# Sheet2.net
KiCad netlist of a schematic drawn in Altium Designer
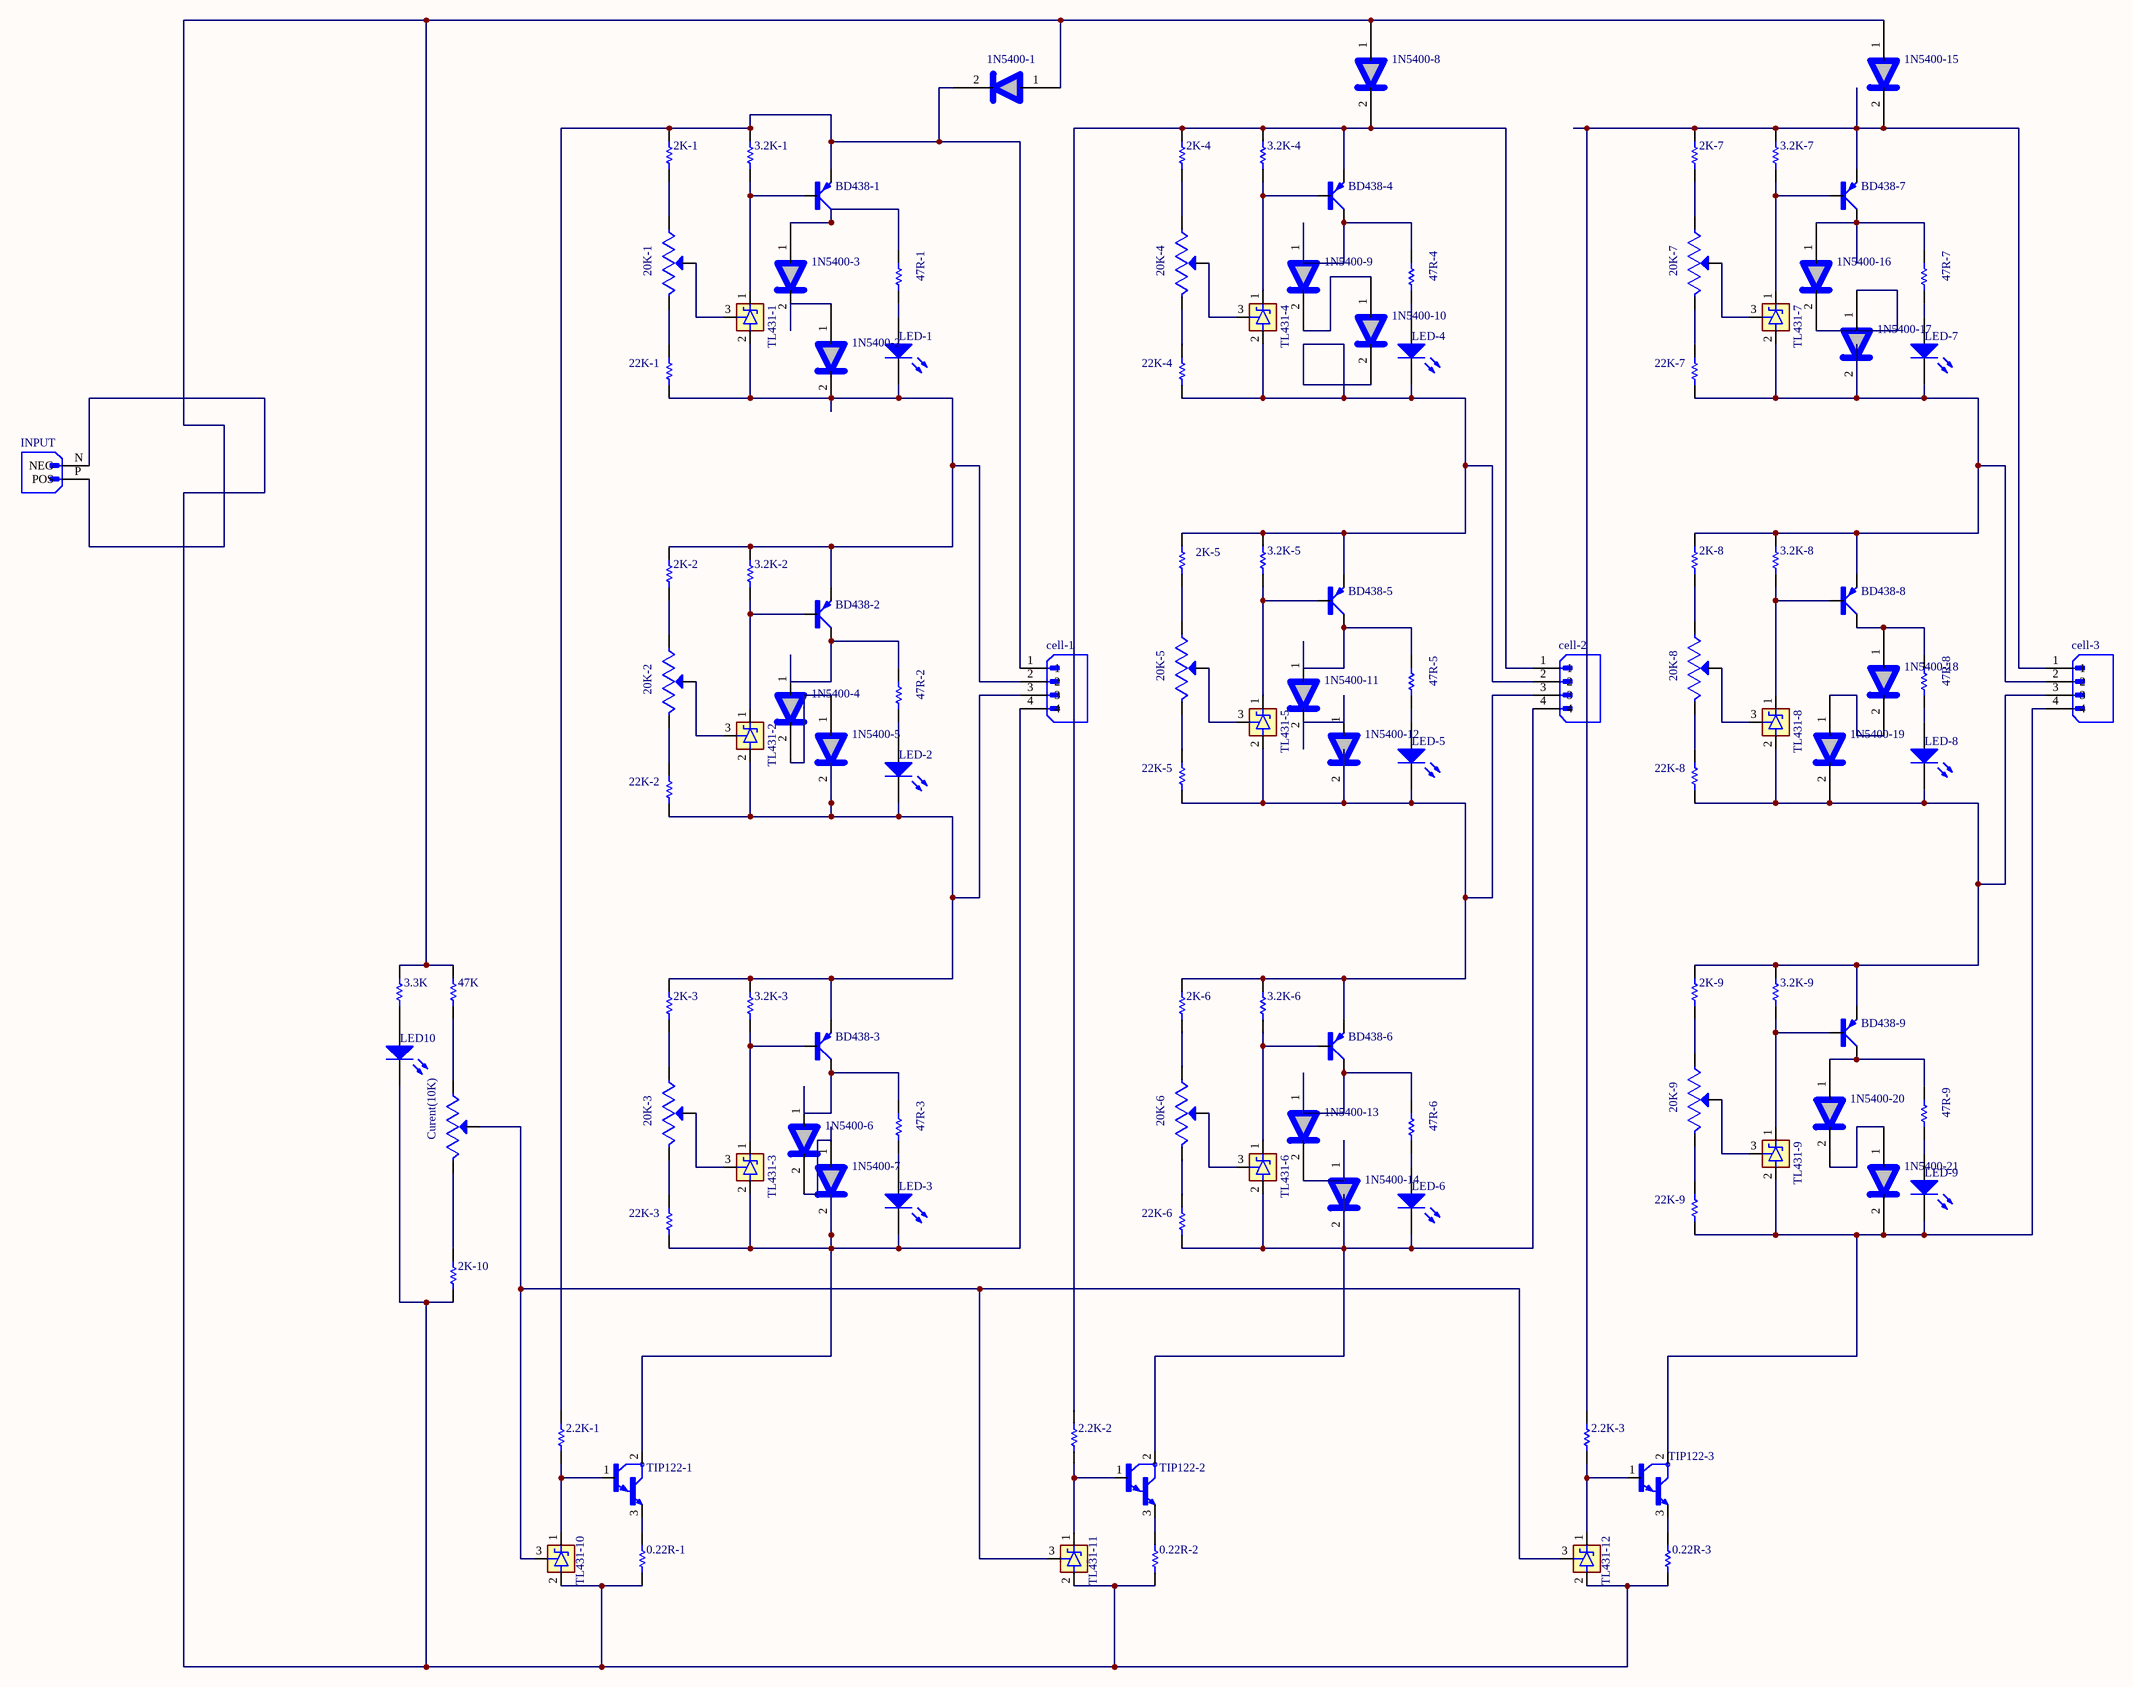
[diagram p0: Sheet2.SchDoc]

(export (version "E")
  (design (tool "Eeschema 10.0.6"))
  (components
    (comp (ref "0.22R-1")
      (value "~")
      (footprint "AXIAL-0.3")
      (description "Resistor")
      (fields (field (name "PUBLISHER") "Altium Limited"))
      (libsource (lib "Miscellaneous Devices") (part "Res1"))
    )
    (comp (ref "0.22R-2")
      (value "~")
      (footprint "AXIAL-0.3")
      (description "Resistor")
      (fields (field (name "PUBLISHER") "Altium Limited"))
      (libsource (lib "Miscellaneous Devices") (part "Res1"))
    )
    (comp (ref "0.22R-3")
      (value "~")
      (footprint "AXIAL-0.3")
      (description "Resistor")
      (fields (field (name "PUBLISHER") "Altium Limited"))
      (libsource (lib "Miscellaneous Devices") (part "Res1"))
    )
    (comp (ref "1N5400-1")
      (value "~")
      (footprint "PCBComponent_1")
      (libsource (lib "Schlib1") (part "1N5400-"))
    )
    (comp (ref "1N5400-2")
      (value "~")
      (footprint "PCBComponent_1")
      (libsource (lib "Schlib1") (part "1N5400-"))
    )
    (comp (ref "1N5400-3")
      (value "~")
      (footprint "PCBComponent_1")
      (libsource (lib "Schlib1") (part "1N5400-"))
    )
    (comp (ref "1N5400-4")
      (value "~")
      (footprint "PCBComponent_1")
      (libsource (lib "Schlib1") (part "1N5400-"))
    )
    (comp (ref "1N5400-5")
      (value "~")
      (footprint "PCBComponent_1")
      (libsource (lib "Schlib1") (part "1N5400-"))
    )
    (comp (ref "1N5400-6")
      (value "~")
      (footprint "PCBComponent_1")
      (libsource (lib "Schlib1") (part "1N5400-"))
    )
    (comp (ref "1N5400-7")
      (value "~")
      (footprint "PCBComponent_1")
      (libsource (lib "Schlib1") (part "1N5400-"))
    )
    (comp (ref "1N5400-8")
      (value "~")
      (footprint "PCBComponent_1")
      (libsource (lib "Schlib1") (part "1N5400-"))
    )
    (comp (ref "1N5400-9")
      (value "~")
      (footprint "PCBComponent_1")
      (libsource (lib "Schlib1") (part "1N5400-"))
    )
    (comp (ref "1N5400-10")
      (value "~")
      (footprint "PCBComponent_1")
      (libsource (lib "Schlib1") (part "1N5400-"))
    )
    (comp (ref "1N5400-11")
      (value "~")
      (footprint "PCBComponent_1")
      (libsource (lib "Schlib1") (part "1N5400-"))
    )
    (comp (ref "1N5400-12")
      (value "~")
      (footprint "PCBComponent_1")
      (libsource (lib "Schlib1") (part "1N5400-"))
    )
    (comp (ref "1N5400-13")
      (value "~")
      (footprint "PCBComponent_1")
      (libsource (lib "Schlib1") (part "1N5400-"))
    )
    (comp (ref "1N5400-14")
      (value "~")
      (footprint "PCBComponent_1")
      (libsource (lib "Schlib1") (part "1N5400-"))
    )
    (comp (ref "1N5400-15")
      (value "~")
      (footprint "PCBComponent_1")
      (libsource (lib "Schlib1") (part "1N5400-"))
    )
    (comp (ref "1N5400-16")
      (value "~")
      (footprint "PCBComponent_1")
      (libsource (lib "Schlib1") (part "1N5400-"))
    )
    (comp (ref "1N5400-17")
      (value "~")
      (footprint "PCBComponent_1")
      (libsource (lib "Schlib1") (part "1N5400-"))
    )
    (comp (ref "1N5400-18")
      (value "~")
      (footprint "PCBComponent_1")
      (libsource (lib "Schlib1") (part "1N5400-"))
    )
    (comp (ref "1N5400-19")
      (value "~")
      (footprint "PCBComponent_1")
      (libsource (lib "Schlib1") (part "1N5400-"))
    )
    (comp (ref "1N5400-20")
      (value "~")
      (footprint "PCBComponent_1")
      (libsource (lib "Schlib1") (part "1N5400-"))
    )
    (comp (ref "1N5400-21")
      (value "~")
      (footprint "PCBComponent_1")
      (libsource (lib "Schlib1") (part "1N5400-"))
    )
    (comp (ref "2.2K-1")
      (value "~")
      (footprint "AXIAL-0.3")
      (description "Resistor")
      (fields (field (name "PUBLISHER") "Altium Limited"))
      (libsource (lib "Miscellaneous Devices") (part "Res1"))
    )
    (comp (ref "2.2K-2")
      (value "~")
      (footprint "AXIAL-0.3")
      (description "Resistor")
      (fields (field (name "PUBLISHER") "Altium Limited"))
      (libsource (lib "Miscellaneous Devices") (part "Res1"))
    )
    (comp (ref "2.2K-3")
      (value "~")
      (footprint "AXIAL-0.3")
      (description "Resistor")
      (fields (field (name "PUBLISHER") "Altium Limited"))
      (libsource (lib "Miscellaneous Devices") (part "Res1"))
    )
    (comp (ref "2K-1")
      (value "~")
      (footprint "AXIAL-0.3")
      (description "Resistor")
      (fields (field (name "PUBLISHER") "Altium Limited"))
      (libsource (lib "Miscellaneous Devices") (part "Res1"))
    )
    (comp (ref "2K-2")
      (value "~")
      (footprint "AXIAL-0.3")
      (description "Resistor")
      (fields (field (name "PUBLISHER") "Altium Limited"))
      (libsource (lib "Miscellaneous Devices") (part "Res1"))
    )
    (comp (ref "2K-3")
      (value "~")
      (footprint "AXIAL-0.3")
      (description "Resistor")
      (fields (field (name "PUBLISHER") "Altium Limited"))
      (libsource (lib "Miscellaneous Devices") (part "Res1"))
    )
    (comp (ref "2K-4")
      (value "~")
      (footprint "AXIAL-0.3")
      (description "Resistor")
      (fields (field (name "PUBLISHER") "Altium Limited"))
      (libsource (lib "Miscellaneous Devices") (part "Res1"))
    )
    (comp (ref "2K-5")
      (value "~")
      (footprint "AXIAL-0.3")
      (description "Resistor")
      (fields (field (name "PUBLISHER") "Altium Limited"))
      (libsource (lib "Miscellaneous Devices") (part "Res1"))
    )
    (comp (ref "2K-6")
      (value "~")
      (footprint "AXIAL-0.3")
      (description "Resistor")
      (fields (field (name "PUBLISHER") "Altium Limited"))
      (libsource (lib "Miscellaneous Devices") (part "Res1"))
    )
    (comp (ref "2K-7")
      (value "~")
      (footprint "AXIAL-0.3")
      (description "Resistor")
      (fields (field (name "PUBLISHER") "Altium Limited"))
      (libsource (lib "Miscellaneous Devices") (part "Res1"))
    )
    (comp (ref "2K-8")
      (value "~")
      (footprint "AXIAL-0.3")
      (description "Resistor")
      (fields (field (name "PUBLISHER") "Altium Limited"))
      (libsource (lib "Miscellaneous Devices") (part "Res1"))
    )
    (comp (ref "2K-9")
      (value "~")
      (footprint "AXIAL-0.3")
      (description "Resistor")
      (fields (field (name "PUBLISHER") "Altium Limited"))
      (libsource (lib "Miscellaneous Devices") (part "Res1"))
    )
    (comp (ref "2K-10")
      (value "~")
      (footprint "AXIAL-0.3")
      (description "Resistor")
      (fields (field (name "PUBLISHER") "Altium Limited"))
      (libsource (lib "Miscellaneous Devices") (part "Res1"))
    )
    (comp (ref "3.2K-1")
      (value "~")
      (footprint "AXIAL-0.3")
      (description "Resistor")
      (fields (field (name "PUBLISHER") "Altium Limited"))
      (libsource (lib "Miscellaneous Devices") (part "Res1"))
    )
    (comp (ref "3.2K-2")
      (value "~")
      (footprint "AXIAL-0.3")
      (description "Resistor")
      (fields (field (name "PUBLISHER") "Altium Limited"))
      (libsource (lib "Miscellaneous Devices") (part "Res1"))
    )
    (comp (ref "3.2K-3")
      (value "~")
      (footprint "AXIAL-0.3")
      (description "Resistor")
      (fields (field (name "PUBLISHER") "Altium Limited"))
      (libsource (lib "Miscellaneous Devices") (part "Res1"))
    )
    (comp (ref "3.2K-4")
      (value "~")
      (footprint "AXIAL-0.3")
      (description "Resistor")
      (fields (field (name "PUBLISHER") "Altium Limited"))
      (libsource (lib "Miscellaneous Devices") (part "Res1"))
    )
    (comp (ref "3.2K-5")
      (value "~")
      (footprint "AXIAL-0.3")
      (description "Resistor")
      (fields (field (name "PUBLISHER") "Altium Limited"))
      (libsource (lib "Miscellaneous Devices") (part "Res1"))
    )
    (comp (ref "3.2K-6")
      (value "~")
      (footprint "AXIAL-0.3")
      (description "Resistor")
      (fields (field (name "PUBLISHER") "Altium Limited"))
      (libsource (lib "Miscellaneous Devices") (part "Res1"))
    )
    (comp (ref "3.2K-7")
      (value "~")
      (footprint "AXIAL-0.3")
      (description "Resistor")
      (fields (field (name "PUBLISHER") "Altium Limited"))
      (libsource (lib "Miscellaneous Devices") (part "Res1"))
    )
    (comp (ref "3.2K-8")
      (value "~")
      (footprint "AXIAL-0.3")
      (description "Resistor")
      (fields (field (name "PUBLISHER") "Altium Limited"))
      (libsource (lib "Miscellaneous Devices") (part "Res1"))
    )
    (comp (ref "3.2K-9")
      (value "~")
      (footprint "AXIAL-0.3")
      (description "Resistor")
      (fields (field (name "PUBLISHER") "Altium Limited"))
      (libsource (lib "Miscellaneous Devices") (part "Res1"))
    )
    (comp (ref "3.3K")
      (value "~")
      (footprint "AXIAL-0.3")
      (description "Resistor")
      (fields (field (name "PUBLISHER") "Altium Limited"))
      (libsource (lib "Miscellaneous Devices") (part "Res1"))
    )
    (comp (ref "20K-1")
      (value "~")
      (footprint "TRIM_3296W-FM1-502")
      (description "Trimmer Resistors - Through Hole")
      (fields (field (name "MP") "3296W-FM1-502") (field (name "MF") "Bourns"))
      (libsource (lib "3296W-FM1-502") (part "3296W-FM1-502"))
    )
    (comp (ref "20K-2")
      (value "~")
      (footprint "TRIM_3296W-FM1-502")
      (description "Trimmer Resistors - Through Hole")
      (fields (field (name "MP") "3296W-FM1-502") (field (name "MF") "Bourns"))
      (libsource (lib "3296W-FM1-502") (part "3296W-FM1-502"))
    )
    (comp (ref "20K-3")
      (value "~")
      (footprint "TRIM_3296W-FM1-502")
      (description "Trimmer Resistors - Through Hole")
      (fields (field (name "MP") "3296W-FM1-502") (field (name "MF") "Bourns"))
      (libsource (lib "3296W-FM1-502") (part "3296W-FM1-502"))
    )
    (comp (ref "20K-4")
      (value "~")
      (footprint "TRIM_3296W-FM1-502")
      (description "Trimmer Resistors - Through Hole")
      (fields (field (name "MP") "3296W-FM1-502") (field (name "MF") "Bourns"))
      (libsource (lib "3296W-FM1-502") (part "3296W-FM1-502"))
    )
    (comp (ref "20K-5")
      (value "~")
      (footprint "TRIM_3296W-FM1-502")
      (description "Trimmer Resistors - Through Hole")
      (fields (field (name "MP") "3296W-FM1-502") (field (name "MF") "Bourns"))
      (libsource (lib "3296W-FM1-502") (part "3296W-FM1-502"))
    )
    (comp (ref "20K-6")
      (value "~")
      (footprint "TRIM_3296W-FM1-502")
      (description "Trimmer Resistors - Through Hole")
      (fields (field (name "MP") "3296W-FM1-502") (field (name "MF") "Bourns"))
      (libsource (lib "3296W-FM1-502") (part "3296W-FM1-502"))
    )
    (comp (ref "20K-7")
      (value "~")
      (footprint "TRIM_3296W-FM1-502")
      (description "Trimmer Resistors - Through Hole")
      (fields (field (name "MP") "3296W-FM1-502") (field (name "MF") "Bourns"))
      (libsource (lib "3296W-FM1-502") (part "3296W-FM1-502"))
    )
    (comp (ref "20K-8")
      (value "~")
      (footprint "TRIM_3296W-FM1-502")
      (description "Trimmer Resistors - Through Hole")
      (fields (field (name "MP") "3296W-FM1-502") (field (name "MF") "Bourns"))
      (libsource (lib "3296W-FM1-502") (part "3296W-FM1-502"))
    )
    (comp (ref "20K-9")
      (value "~")
      (footprint "TRIM_3296W-FM1-502")
      (description "Trimmer Resistors - Through Hole")
      (fields (field (name "MP") "3296W-FM1-502") (field (name "MF") "Bourns"))
      (libsource (lib "3296W-FM1-502") (part "3296W-FM1-502"))
    )
    (comp (ref "22K-1")
      (value "~")
      (footprint "AXIAL-0.3")
      (description "Resistor")
      (fields (field (name "PUBLISHER") "Altium Limited"))
      (libsource (lib "Miscellaneous Devices") (part "Res1"))
    )
    (comp (ref "22K-2")
      (value "~")
      (footprint "AXIAL-0.3")
      (description "Resistor")
      (fields (field (name "PUBLISHER") "Altium Limited"))
      (libsource (lib "Miscellaneous Devices") (part "Res1"))
    )
    (comp (ref "22K-3")
      (value "~")
      (footprint "AXIAL-0.3")
      (description "Resistor")
      (fields (field (name "PUBLISHER") "Altium Limited"))
      (libsource (lib "Miscellaneous Devices") (part "Res1"))
    )
    (comp (ref "22K-4")
      (value "~")
      (footprint "AXIAL-0.3")
      (description "Resistor")
      (fields (field (name "PUBLISHER") "Altium Limited"))
      (libsource (lib "Miscellaneous Devices") (part "Res1"))
    )
    (comp (ref "22K-5")
      (value "~")
      (footprint "AXIAL-0.3")
      (description "Resistor")
      (fields (field (name "PUBLISHER") "Altium Limited"))
      (libsource (lib "Miscellaneous Devices") (part "Res1"))
    )
    (comp (ref "22K-6")
      (value "~")
      (footprint "AXIAL-0.3")
      (description "Resistor")
      (fields (field (name "PUBLISHER") "Altium Limited"))
      (libsource (lib "Miscellaneous Devices") (part "Res1"))
    )
    (comp (ref "22K-7")
      (value "~")
      (footprint "AXIAL-0.3")
      (description "Resistor")
      (fields (field (name "PUBLISHER") "Altium Limited"))
      (libsource (lib "Miscellaneous Devices") (part "Res1"))
    )
    (comp (ref "22K-8")
      (value "~")
      (footprint "AXIAL-0.3")
      (description "Resistor")
      (fields (field (name "PUBLISHER") "Altium Limited"))
      (libsource (lib "Miscellaneous Devices") (part "Res1"))
    )
    (comp (ref "22K-9")
      (value "~")
      (footprint "AXIAL-0.3")
      (description "Resistor")
      (fields (field (name "PUBLISHER") "Altium Limited"))
      (libsource (lib "Miscellaneous Devices") (part "Res1"))
    )
    (comp (ref "47K")
      (value "~")
      (footprint "AXIAL-0.3")
      (description "Resistor")
      (fields (field (name "PUBLISHER") "Altium Limited"))
      (libsource (lib "Miscellaneous Devices") (part "Res1"))
    )
    (comp (ref "47R-1")
      (value "~")
      (footprint "AXIAL-0.3")
      (description "Resistor")
      (fields (field (name "PUBLISHER") "Altium Limited"))
      (libsource (lib "Miscellaneous Devices") (part "Res1"))
    )
    (comp (ref "47R-2")
      (value "~")
      (footprint "AXIAL-0.3")
      (description "Resistor")
      (fields (field (name "PUBLISHER") "Altium Limited"))
      (libsource (lib "Miscellaneous Devices") (part "Res1"))
    )
    (comp (ref "47R-3")
      (value "~")
      (footprint "AXIAL-0.3")
      (description "Resistor")
      (fields (field (name "PUBLISHER") "Altium Limited"))
      (libsource (lib "Miscellaneous Devices") (part "Res1"))
    )
    (comp (ref "47R-4")
      (value "~")
      (footprint "AXIAL-0.3")
      (description "Resistor")
      (fields (field (name "PUBLISHER") "Altium Limited"))
      (libsource (lib "Miscellaneous Devices") (part "Res1"))
    )
    (comp (ref "47R-5")
      (value "~")
      (footprint "AXIAL-0.3")
      (description "Resistor")
      (fields (field (name "PUBLISHER") "Altium Limited"))
      (libsource (lib "Miscellaneous Devices") (part "Res1"))
    )
    (comp (ref "47R-6")
      (value "~")
      (footprint "AXIAL-0.3")
      (description "Resistor")
      (fields (field (name "PUBLISHER") "Altium Limited"))
      (libsource (lib "Miscellaneous Devices") (part "Res1"))
    )
    (comp (ref "47R-7")
      (value "~")
      (footprint "AXIAL-0.3")
      (description "Resistor")
      (fields (field (name "PUBLISHER") "Altium Limited"))
      (libsource (lib "Miscellaneous Devices") (part "Res1"))
    )
    (comp (ref "47R-8")
      (value "~")
      (footprint "AXIAL-0.3")
      (description "Resistor")
      (fields (field (name "PUBLISHER") "Altium Limited"))
      (libsource (lib "Miscellaneous Devices") (part "Res1"))
    )
    (comp (ref "47R-9")
      (value "~")
      (footprint "AXIAL-0.3")
      (description "Resistor")
      (fields (field (name "PUBLISHER") "Altium Limited"))
      (libsource (lib "Miscellaneous Devices") (part "Res1"))
    )
    (comp (ref "BD438-1")
      (value "~")
      (footprint "TO126AV")
      (description "Bipolar (BJT) Transistor PNP 45V 4A 3MHz 36W Through Hole SOT-32-3")
      (fields (field (name "MF") "ON") (field (name "MP") "BD438"))
      (libsource (lib "BD438") (part "BD438"))
    )
    (comp (ref "BD438-2")
      (value "~")
      (footprint "TO126AV")
      (description "Bipolar (BJT) Transistor PNP 45V 4A 3MHz 36W Through Hole SOT-32-3")
      (fields (field (name "MF") "ON") (field (name "MP") "BD438"))
      (libsource (lib "BD438") (part "BD438"))
    )
    (comp (ref "BD438-3")
      (value "~")
      (footprint "TO126AV")
      (description "Bipolar (BJT) Transistor PNP 45V 4A 3MHz 36W Through Hole SOT-32-3")
      (fields (field (name "MF") "ON") (field (name "MP") "BD438"))
      (libsource (lib "BD438") (part "BD438"))
    )
    (comp (ref "BD438-4")
      (value "~")
      (footprint "TO126AV")
      (description "Bipolar (BJT) Transistor PNP 45V 4A 3MHz 36W Through Hole SOT-32-3")
      (fields (field (name "MF") "ON") (field (name "MP") "BD438"))
      (libsource (lib "BD438") (part "BD438"))
    )
    (comp (ref "BD438-5")
      (value "~")
      (footprint "TO126AV")
      (description "Bipolar (BJT) Transistor PNP 45V 4A 3MHz 36W Through Hole SOT-32-3")
      (fields (field (name "MF") "ON") (field (name "MP") "BD438"))
      (libsource (lib "BD438") (part "BD438"))
    )
    (comp (ref "BD438-6")
      (value "~")
      (footprint "TO126AV")
      (description "Bipolar (BJT) Transistor PNP 45V 4A 3MHz 36W Through Hole SOT-32-3")
      (fields (field (name "MF") "ON") (field (name "MP") "BD438"))
      (libsource (lib "BD438") (part "BD438"))
    )
    (comp (ref "BD438-7")
      (value "~")
      (footprint "TO126AV")
      (description "Bipolar (BJT) Transistor PNP 45V 4A 3MHz 36W Through Hole SOT-32-3")
      (fields (field (name "MF") "ON") (field (name "MP") "BD438"))
      (libsource (lib "BD438") (part "BD438"))
    )
    (comp (ref "BD438-8")
      (value "~")
      (footprint "TO126AV")
      (description "Bipolar (BJT) Transistor PNP 45V 4A 3MHz 36W Through Hole SOT-32-3")
      (fields (field (name "MF") "ON") (field (name "MP") "BD438"))
      (libsource (lib "BD438") (part "BD438"))
    )
    (comp (ref "BD438-9")
      (value "~")
      (footprint "TO126AV")
      (description "Bipolar (BJT) Transistor PNP 45V 4A 3MHz 36W Through Hole SOT-32-3")
      (fields (field (name "MF") "ON") (field (name "MP") "BD438"))
      (libsource (lib "BD438") (part "BD438"))
    )
    (comp (ref "cell-1")
      (value "~")
      (footprint "JST_B4B-XH-A(LF)(SN)")
      (description "Connector Header Through Hole 4 position 0.098 (2.50mm)")
      (fields (field (name "MP") "B4B-XH-A(LF)(SN)") (field (name "MF") "JST Sales"))
      (libsource (lib "B4B-XH-A_LF__SN_") (part "B4B-XH-A(LF)(SN)"))
    )
    (comp (ref "cell-2")
      (value "~")
      (footprint "JST_B4B-XH-A(LF)(SN)")
      (description "Connector Header Through Hole 4 position 0.098 (2.50mm)")
      (fields (field (name "MP") "B4B-XH-A(LF)(SN)") (field (name "MF") "JST Sales"))
      (libsource (lib "B4B-XH-A_LF__SN_") (part "B4B-XH-A(LF)(SN)"))
    )
    (comp (ref "cell-3")
      (value "~")
      (footprint "JST_B4B-XH-A(LF)(SN)")
      (description "Connector Header Through Hole 4 position 0.098 (2.50mm)")
      (fields (field (name "MP") "B4B-XH-A(LF)(SN)") (field (name "MF") "JST Sales"))
      (libsource (lib "B4B-XH-A_LF__SN_") (part "B4B-XH-A(LF)(SN)"))
    )
    (comp (ref "Curent(10K)")
      (value "~")
      (footprint "TRIM_3296W-FM1-502")
      (description "Trimmer Resistors - Through Hole")
      (fields (field (name "MP") "3296W-FM1-502") (field (name "MF") "Bourns"))
      (libsource (lib "3296W-FM1-502") (part "3296W-FM1-502"))
    )
    (comp (ref "INPUT")
      (value "~")
      (footprint "AMASS_XT60-M")
      (description "Plug; DC supply; XT60; male; PIN: 2; for cable; soldered; 30A; 500V")
      (fields (field (name "MP") "XT60-M") (field (name "MF") "AMASS"))
      (libsource (lib "XT60-M") (part "XT60-M"))
    )
    (comp (ref "LED-1")
      (value "~")
      (footprint "LED-1")
      (description "Typical RED GaAs LED")
      (fields (field (name "PUBLISHER") "Altium Limited"))
      (libsource (lib "Miscellaneous Devices") (part "LED1"))
    )
    (comp (ref "LED-2")
      (value "~")
      (footprint "LED-1")
      (description "Typical RED GaAs LED")
      (fields (field (name "PUBLISHER") "Altium Limited"))
      (libsource (lib "Miscellaneous Devices") (part "LED1"))
    )
    (comp (ref "LED-3")
      (value "~")
      (footprint "LED-1")
      (description "Typical RED GaAs LED")
      (fields (field (name "PUBLISHER") "Altium Limited"))
      (libsource (lib "Miscellaneous Devices") (part "LED1"))
    )
    (comp (ref "LED-4")
      (value "~")
      (footprint "LED-1")
      (description "Typical RED GaAs LED")
      (fields (field (name "PUBLISHER") "Altium Limited"))
      (libsource (lib "Miscellaneous Devices") (part "LED1"))
    )
    (comp (ref "LED-5")
      (value "~")
      (footprint "LED-1")
      (description "Typical RED GaAs LED")
      (fields (field (name "PUBLISHER") "Altium Limited"))
      (libsource (lib "Miscellaneous Devices") (part "LED1"))
    )
    (comp (ref "LED-6")
      (value "~")
      (footprint "LED-1")
      (description "Typical RED GaAs LED")
      (fields (field (name "PUBLISHER") "Altium Limited"))
      (libsource (lib "Miscellaneous Devices") (part "LED1"))
    )
    (comp (ref "LED-7")
      (value "~")
      (footprint "LED-1")
      (description "Typical RED GaAs LED")
      (fields (field (name "PUBLISHER") "Altium Limited"))
      (libsource (lib "Miscellaneous Devices") (part "LED1"))
    )
    (comp (ref "LED-8")
      (value "~")
      (footprint "LED-1")
      (description "Typical RED GaAs LED")
      (fields (field (name "PUBLISHER") "Altium Limited"))
      (libsource (lib "Miscellaneous Devices") (part "LED1"))
    )
    (comp (ref "LED-9")
      (value "~")
      (footprint "LED-1")
      (description "Typical RED GaAs LED")
      (fields (field (name "PUBLISHER") "Altium Limited"))
      (libsource (lib "Miscellaneous Devices") (part "LED1"))
    )
    (comp (ref "LED10")
      (value "~")
      (footprint "LED-1")
      (description "Typical RED GaAs LED")
      (fields (field (name "PUBLISHER") "Altium Limited"))
      (libsource (lib "Miscellaneous Devices") (part "LED1"))
    )
    (comp (ref "TIP122-1")
      (value "~")
      (footprint "TO254P1009X445X1985-3")
      (description "Bipolar (BJT) Transistor NPN - Darlington 100V 5A 2W Through Hole TO-220AB")
      (fields (field (name "MF") "ON Semiconductor") (field (name "MP") "TIP122G"))
      (libsource (lib "TIP122G") (part "TIP122G"))
    )
    (comp (ref "TIP122-2")
      (value "~")
      (footprint "TO254P1009X445X1985-3")
      (description "Bipolar (BJT) Transistor NPN - Darlington 100V 5A 2W Through Hole TO-220AB")
      (fields (field (name "MF") "ON Semiconductor") (field (name "MP") "TIP122G"))
      (libsource (lib "TIP122G") (part "TIP122G"))
    )
    (comp (ref "TIP122-3")
      (value "~")
      (footprint "TO254P1009X445X1985-3")
      (description "Bipolar (BJT) Transistor NPN - Darlington 100V 5A 2W Through Hole TO-220AB")
      (fields (field (name "MF") "ON Semiconductor") (field (name "MP") "TIP122G"))
      (libsource (lib "TIP122G") (part "TIP122G"))
    )
    (comp (ref "TL431-1")
      (value "~")
      (footprint "TO-92")
      (description "Adjustable precision shunt regulator 3-TO-92 0 to 70")
      (fields (field (name "MP") "TL431CLP"))
      (libsource (lib "TL431CLP") (part "TL431CLP"))
    )
    (comp (ref "TL431-2")
      (value "~")
      (footprint "TO-92")
      (description "Adjustable precision shunt regulator 3-TO-92 0 to 70")
      (fields (field (name "MP") "TL431CLP"))
      (libsource (lib "TL431CLP") (part "TL431CLP"))
    )
    (comp (ref "TL431-3")
      (value "~")
      (footprint "TO-92")
      (description "Adjustable precision shunt regulator 3-TO-92 0 to 70")
      (fields (field (name "MP") "TL431CLP"))
      (libsource (lib "TL431CLP") (part "TL431CLP"))
    )
    (comp (ref "TL431-4")
      (value "~")
      (footprint "TO-92")
      (description "Adjustable precision shunt regulator 3-TO-92 0 to 70")
      (fields (field (name "MP") "TL431CLP"))
      (libsource (lib "TL431CLP") (part "TL431CLP"))
    )
    (comp (ref "TL431-5")
      (value "~")
      (footprint "TO-92")
      (description "Adjustable precision shunt regulator 3-TO-92 0 to 70")
      (fields (field (name "MP") "TL431CLP"))
      (libsource (lib "TL431CLP") (part "TL431CLP"))
    )
    (comp (ref "TL431-6")
      (value "~")
      (footprint "TO-92")
      (description "Adjustable precision shunt regulator 3-TO-92 0 to 70")
      (fields (field (name "MP") "TL431CLP"))
      (libsource (lib "TL431CLP") (part "TL431CLP"))
    )
    (comp (ref "TL431-7")
      (value "~")
      (footprint "TO-92")
      (description "Adjustable precision shunt regulator 3-TO-92 0 to 70")
      (fields (field (name "MP") "TL431CLP"))
      (libsource (lib "TL431CLP") (part "TL431CLP"))
    )
    (comp (ref "TL431-8")
      (value "~")
      (footprint "TO-92")
      (description "Adjustable precision shunt regulator 3-TO-92 0 to 70")
      (fields (field (name "MP") "TL431CLP"))
      (libsource (lib "TL431CLP") (part "TL431CLP"))
    )
    (comp (ref "TL431-9")
      (value "~")
      (footprint "TO-92")
      (description "Adjustable precision shunt regulator 3-TO-92 0 to 70")
      (fields (field (name "MP") "TL431CLP"))
      (libsource (lib "TL431CLP") (part "TL431CLP"))
    )
    (comp (ref "TL431-10")
      (value "~")
      (footprint "TO-92")
      (description "Adjustable precision shunt regulator 3-TO-92 0 to 70")
      (fields (field (name "MP") "TL431CLP"))
      (libsource (lib "TL431CLP") (part "TL431CLP"))
    )
    (comp (ref "TL431-11")
      (value "~")
      (footprint "TO-92")
      (description "Adjustable precision shunt regulator 3-TO-92 0 to 70")
      (fields (field (name "MP") "TL431CLP"))
      (libsource (lib "TL431CLP") (part "TL431CLP"))
    )
    (comp (ref "TL431-12")
      (value "~")
      (footprint "TO-92")
      (description "Adjustable precision shunt regulator 3-TO-92 0 to 70")
      (fields (field (name "MP") "TL431CLP"))
      (libsource (lib "TL431CLP") (part "TL431CLP"))
    )
  )
  (nets
    (net (code "1") (name "Net-(1N5400-1-Pad2)") (class "Default")
      (node (ref "1N5400-1") (pin "2") (pintype "passive"))
      (node (ref "2.2K-1") (pin "2") (pinfunction "2_2") (pintype "passive"))
      (node (ref "2K-1") (pin "2") (pinfunction "2_2") (pintype "passive"))
      (node (ref "3.2K-1") (pin "1") (pinfunction "1_1") (pintype "passive"))
      (node (ref "BD438-1") (pin "E") (pinfunction "E_E") (pintype "passive"))
      (node (ref "cell-1") (pin "1") (pinfunction "1_1") (pintype "passive"))
    )
    (net (code "2") (name "Net-(1N5400-2-Pad1)") (class "Default")
      (node (ref "1N5400-2") (pin "1") (pintype "passive"))
      (node (ref "1N5400-3") (pin "2") (pintype "passive"))
    )
    (net (code "3") (name "Net-(1N5400-3-Pad1)") (class "Default")
      (node (ref "1N5400-3") (pin "1") (pintype "passive"))
      (node (ref "47R-1") (pin "1") (pinfunction "1_1") (pintype "passive"))
      (node (ref "BD438-1") (pin "C") (pinfunction "C_C") (pintype "passive"))
    )
    (net (code "4") (name "Net-(1N5400-4-Pad1)") (class "Default")
      (node (ref "1N5400-4") (pin "1") (pintype "passive"))
      (node (ref "47R-2") (pin "1") (pinfunction "1_1") (pintype "passive"))
      (node (ref "BD438-2") (pin "C") (pinfunction "C_C") (pintype "passive"))
    )
    (net (code "5") (name "Net-(1N5400-4-Pad2)") (class "Default")
      (node (ref "1N5400-4") (pin "2") (pintype "passive"))
      (node (ref "1N5400-5") (pin "1") (pintype "passive"))
    )
    (net (code "6") (name "Net-(1N5400-6-Pad1)") (class "Default")
      (node (ref "1N5400-6") (pin "1") (pintype "passive"))
      (node (ref "47R-3") (pin "1") (pinfunction "1_1") (pintype "passive"))
      (node (ref "BD438-3") (pin "C") (pinfunction "C_C") (pintype "passive"))
    )
    (net (code "7") (name "Net-(1N5400-6-Pad2)") (class "Default")
      (node (ref "1N5400-6") (pin "2") (pintype "passive"))
      (node (ref "1N5400-7") (pin "1") (pintype "passive"))
    )
    (net (code "8") (name "Net-(1N5400-8-Pad2)") (class "Default")
      (node (ref "1N5400-8") (pin "2") (pintype "passive"))
      (node (ref "2.2K-2") (pin "2") (pinfunction "2_2") (pintype "passive"))
      (node (ref "2K-4") (pin "2") (pinfunction "2_2") (pintype "passive"))
      (node (ref "3.2K-4") (pin "1") (pinfunction "1_1") (pintype "passive"))
      (node (ref "BD438-4") (pin "E") (pinfunction "E_E") (pintype "passive"))
      (node (ref "cell-2") (pin "1") (pinfunction "1_1") (pintype "passive"))
    )
    (net (code "9") (name "Net-(1N5400-9-Pad1)") (class "Default")
      (node (ref "1N5400-9") (pin "1") (pintype "passive"))
      (node (ref "47R-4") (pin "1") (pinfunction "1_1") (pintype "passive"))
      (node (ref "BD438-4") (pin "C") (pinfunction "C_C") (pintype "passive"))
    )
    (net (code "10") (name "Net-(1N5400-10-Pad1)") (class "Default")
      (node (ref "1N5400-10") (pin "1") (pintype "passive"))
      (node (ref "1N5400-9") (pin "2") (pintype "passive"))
    )
    (net (code "11") (name "Net-(1N5400-11-Pad1)") (class "Default")
      (node (ref "1N5400-11") (pin "1") (pintype "passive"))
      (node (ref "47R-5") (pin "1") (pinfunction "1_1") (pintype "passive"))
      (node (ref "BD438-5") (pin "C") (pinfunction "C_C") (pintype "passive"))
    )
    (net (code "12") (name "Net-(1N5400-11-Pad2)") (class "Default")
      (node (ref "1N5400-11") (pin "2") (pintype "passive"))
      (node (ref "1N5400-12") (pin "1") (pintype "passive"))
    )
    (net (code "13") (name "Net-(1N5400-13-Pad1)") (class "Default")
      (node (ref "1N5400-13") (pin "1") (pintype "passive"))
      (node (ref "47R-6") (pin "1") (pinfunction "1_1") (pintype "passive"))
      (node (ref "BD438-6") (pin "C") (pinfunction "C_C") (pintype "passive"))
    )
    (net (code "14") (name "Net-(1N5400-13-Pad2)") (class "Default")
      (node (ref "1N5400-13") (pin "2") (pintype "passive"))
      (node (ref "1N5400-14") (pin "1") (pintype "passive"))
    )
    (net (code "15") (name "Net-(1N5400-15-Pad2)") (class "Default")
      (node (ref "1N5400-15") (pin "2") (pintype "passive"))
      (node (ref "2.2K-3") (pin "2") (pinfunction "2_2") (pintype "passive"))
      (node (ref "2K-7") (pin "2") (pinfunction "2_2") (pintype "passive"))
      (node (ref "3.2K-7") (pin "1") (pinfunction "1_1") (pintype "passive"))
      (node (ref "BD438-7") (pin "E") (pinfunction "E_E") (pintype "passive"))
      (node (ref "cell-3") (pin "1") (pinfunction "1_1") (pintype "passive"))
    )
    (net (code "16") (name "Net-(1N5400-16-Pad1)") (class "Default")
      (node (ref "1N5400-16") (pin "1") (pintype "passive"))
      (node (ref "47R-7") (pin "1") (pinfunction "1_1") (pintype "passive"))
      (node (ref "BD438-7") (pin "C") (pinfunction "C_C") (pintype "passive"))
    )
    (net (code "17") (name "Net-(1N5400-16-Pad2)") (class "Default")
      (node (ref "1N5400-16") (pin "2") (pintype "passive"))
      (node (ref "1N5400-17") (pin "1") (pintype "passive"))
    )
    (net (code "18") (name "Net-(1N5400-18-Pad1)") (class "Default")
      (node (ref "1N5400-18") (pin "1") (pintype "passive"))
      (node (ref "47R-8") (pin "1") (pinfunction "1_1") (pintype "passive"))
      (node (ref "BD438-8") (pin "C") (pinfunction "C_C") (pintype "passive"))
    )
    (net (code "19") (name "Net-(1N5400-18-Pad2)") (class "Default")
      (node (ref "1N5400-18") (pin "2") (pintype "passive"))
      (node (ref "1N5400-19") (pin "1") (pintype "passive"))
    )
    (net (code "20") (name "Net-(1N5400-20-Pad1)") (class "Default")
      (node (ref "1N5400-20") (pin "1") (pintype "passive"))
      (node (ref "47R-9") (pin "1") (pinfunction "1_1") (pintype "passive"))
      (node (ref "BD438-9") (pin "C") (pinfunction "C_C") (pintype "passive"))
    )
    (net (code "21") (name "Net-(1N5400-20-Pad2)") (class "Default")
      (node (ref "1N5400-20") (pin "2") (pintype "passive"))
      (node (ref "1N5400-21") (pin "1") (pintype "passive"))
    )
    (net (code "22") (name "Net-(20K-1-CCW)") (class "Default")
      (node (ref "20K-1") (pin "1") (pinfunction "CCW_1") (pintype "passive"))
      (node (ref "2K-1") (pin "1") (pinfunction "1_1") (pintype "passive"))
    )
    (net (code "23") (name "Net-(20K-1-CW)") (class "Default")
      (node (ref "20K-1") (pin "3") (pinfunction "CW_3") (pintype "passive"))
      (node (ref "22K-1") (pin "1") (pinfunction "1_1") (pintype "passive"))
    )
    (net (code "24") (name "Net-(20K-1-WIPER)") (class "Default")
      (node (ref "20K-1") (pin "2") (pinfunction "WIPER_2") (pintype "passive"))
      (node (ref "TL431-1") (pin "3") (pinfunction "REF_3") (pintype "passive"))
    )
    (net (code "25") (name "Net-(20K-2-CCW)") (class "Default")
      (node (ref "20K-2") (pin "1") (pinfunction "CCW_1") (pintype "passive"))
      (node (ref "2K-2") (pin "1") (pinfunction "1_1") (pintype "passive"))
    )
    (net (code "26") (name "Net-(20K-2-CW)") (class "Default")
      (node (ref "20K-2") (pin "3") (pinfunction "CW_3") (pintype "passive"))
      (node (ref "22K-2") (pin "1") (pinfunction "1_1") (pintype "passive"))
    )
    (net (code "27") (name "Net-(20K-2-WIPER)") (class "Default")
      (node (ref "20K-2") (pin "2") (pinfunction "WIPER_2") (pintype "passive"))
      (node (ref "TL431-2") (pin "3") (pinfunction "REF_3") (pintype "passive"))
    )
    (net (code "28") (name "Net-(20K-3-CCW)") (class "Default")
      (node (ref "20K-3") (pin "1") (pinfunction "CCW_1") (pintype "passive"))
      (node (ref "2K-3") (pin "1") (pinfunction "1_1") (pintype "passive"))
    )
    (net (code "29") (name "Net-(20K-3-CW)") (class "Default")
      (node (ref "20K-3") (pin "3") (pinfunction "CW_3") (pintype "passive"))
      (node (ref "22K-3") (pin "1") (pinfunction "1_1") (pintype "passive"))
    )
    (net (code "30") (name "Net-(20K-3-WIPER)") (class "Default")
      (node (ref "20K-3") (pin "2") (pinfunction "WIPER_2") (pintype "passive"))
      (node (ref "TL431-3") (pin "3") (pinfunction "REF_3") (pintype "passive"))
    )
    (net (code "31") (name "Net-(20K-4-CCW)") (class "Default")
      (node (ref "20K-4") (pin "1") (pinfunction "CCW_1") (pintype "passive"))
      (node (ref "2K-4") (pin "1") (pinfunction "1_1") (pintype "passive"))
    )
    (net (code "32") (name "Net-(20K-4-CW)") (class "Default")
      (node (ref "20K-4") (pin "3") (pinfunction "CW_3") (pintype "passive"))
      (node (ref "22K-4") (pin "1") (pinfunction "1_1") (pintype "passive"))
    )
    (net (code "33") (name "Net-(20K-4-WIPER)") (class "Default")
      (node (ref "20K-4") (pin "2") (pinfunction "WIPER_2") (pintype "passive"))
      (node (ref "TL431-4") (pin "3") (pinfunction "REF_3") (pintype "passive"))
    )
    (net (code "34") (name "Net-(20K-5-CCW)") (class "Default")
      (node (ref "20K-5") (pin "1") (pinfunction "CCW_1") (pintype "passive"))
      (node (ref "2K-5") (pin "1") (pinfunction "1_1") (pintype "passive"))
    )
    (net (code "35") (name "Net-(20K-5-CW)") (class "Default")
      (node (ref "20K-5") (pin "3") (pinfunction "CW_3") (pintype "passive"))
      (node (ref "22K-5") (pin "1") (pinfunction "1_1") (pintype "passive"))
    )
    (net (code "36") (name "Net-(20K-5-WIPER)") (class "Default")
      (node (ref "20K-5") (pin "2") (pinfunction "WIPER_2") (pintype "passive"))
      (node (ref "TL431-5") (pin "3") (pinfunction "REF_3") (pintype "passive"))
    )
    (net (code "37") (name "Net-(20K-6-CCW)") (class "Default")
      (node (ref "20K-6") (pin "1") (pinfunction "CCW_1") (pintype "passive"))
      (node (ref "2K-6") (pin "1") (pinfunction "1_1") (pintype "passive"))
    )
    (net (code "38") (name "Net-(20K-6-CW)") (class "Default")
      (node (ref "20K-6") (pin "3") (pinfunction "CW_3") (pintype "passive"))
      (node (ref "22K-6") (pin "1") (pinfunction "1_1") (pintype "passive"))
    )
    (net (code "39") (name "Net-(20K-6-WIPER)") (class "Default")
      (node (ref "20K-6") (pin "2") (pinfunction "WIPER_2") (pintype "passive"))
      (node (ref "TL431-6") (pin "3") (pinfunction "REF_3") (pintype "passive"))
    )
    (net (code "40") (name "Net-(20K-7-CCW)") (class "Default")
      (node (ref "20K-7") (pin "1") (pinfunction "CCW_1") (pintype "passive"))
      (node (ref "2K-7") (pin "1") (pinfunction "1_1") (pintype "passive"))
    )
    (net (code "41") (name "Net-(20K-7-CW)") (class "Default")
      (node (ref "20K-7") (pin "3") (pinfunction "CW_3") (pintype "passive"))
      (node (ref "22K-7") (pin "1") (pinfunction "1_1") (pintype "passive"))
    )
    (net (code "42") (name "Net-(20K-7-WIPER)") (class "Default")
      (node (ref "20K-7") (pin "2") (pinfunction "WIPER_2") (pintype "passive"))
      (node (ref "TL431-7") (pin "3") (pinfunction "REF_3") (pintype "passive"))
    )
    (net (code "43") (name "Net-(20K-8-CCW)") (class "Default")
      (node (ref "20K-8") (pin "1") (pinfunction "CCW_1") (pintype "passive"))
      (node (ref "2K-8") (pin "1") (pinfunction "1_1") (pintype "passive"))
    )
    (net (code "44") (name "Net-(20K-8-CW)") (class "Default")
      (node (ref "20K-8") (pin "3") (pinfunction "CW_3") (pintype "passive"))
      (node (ref "22K-8") (pin "1") (pinfunction "1_1") (pintype "passive"))
    )
    (net (code "45") (name "Net-(20K-8-WIPER)") (class "Default")
      (node (ref "20K-8") (pin "2") (pinfunction "WIPER_2") (pintype "passive"))
      (node (ref "TL431-8") (pin "3") (pinfunction "REF_3") (pintype "passive"))
    )
    (net (code "46") (name "Net-(20K-9-CCW)") (class "Default")
      (node (ref "20K-9") (pin "1") (pinfunction "CCW_1") (pintype "passive"))
      (node (ref "2K-9") (pin "1") (pinfunction "1_1") (pintype "passive"))
    )
    (net (code "47") (name "Net-(20K-9-CW)") (class "Default")
      (node (ref "20K-9") (pin "3") (pinfunction "CW_3") (pintype "passive"))
      (node (ref "22K-9") (pin "1") (pinfunction "1_1") (pintype "passive"))
    )
    (net (code "48") (name "Net-(20K-9-WIPER)") (class "Default")
      (node (ref "20K-9") (pin "2") (pinfunction "WIPER_2") (pintype "passive"))
      (node (ref "TL431-9") (pin "3") (pinfunction "REF_3") (pintype "passive"))
    )
    (net (code "49") (name "Net-(Curent(10K)-CCW)") (class "Default")
      (node (ref "47K") (pin "1") (pinfunction "1_1") (pintype "passive"))
      (node (ref "Curent(10K)") (pin "1") (pinfunction "CCW_1") (pintype "passive"))
    )
    (net (code "50") (name "Net-(Curent(10K)-CW)") (class "Default")
      (node (ref "2K-10") (pin "2") (pinfunction "2_2") (pintype "passive"))
      (node (ref "Curent(10K)") (pin "3") (pinfunction "CW_3") (pintype "passive"))
    )
    (net (code "51") (name "Net-(Curent(10K)-WIPER)") (class "Default")
      (node (ref "Curent(10K)") (pin "2") (pinfunction "WIPER_2") (pintype "passive"))
      (node (ref "TL431-10") (pin "3") (pinfunction "REF_3") (pintype "passive"))
      (node (ref "TL431-11") (pin "3") (pinfunction "REF_3") (pintype "passive"))
      (node (ref "TL431-12") (pin "3") (pinfunction "REF_3") (pintype "passive"))
    )
    (net (code "52") (name "Net-(INPUT-NEG)") (class "Default")
      (node (ref "0.22R-1") (pin "1") (pinfunction "1_1") (pintype "passive"))
      (node (ref "0.22R-2") (pin "1") (pinfunction "1_1") (pintype "passive"))
      (node (ref "0.22R-3") (pin "1") (pinfunction "1_1") (pintype "passive"))
      (node (ref "2K-10") (pin "1") (pinfunction "1_1") (pintype "passive"))
      (node (ref "INPUT") (pin "N") (pinfunction "NEG_N") (pintype "passive"))
      (node (ref "LED10") (pin "2") (pinfunction "K_2") (pintype "passive"))
      (node (ref "TL431-10") (pin "2") (pinfunction "ANODE_2") (pintype "passive"))
      (node (ref "TL431-11") (pin "2") (pinfunction "ANODE_2") (pintype "passive"))
      (node (ref "TL431-12") (pin "2") (pinfunction "ANODE_2") (pintype "passive"))
    )
    (net (code "53") (name "Net-(INPUT-POS)") (class "Default")
      (node (ref "1N5400-1") (pin "1") (pintype "passive"))
      (node (ref "1N5400-15") (pin "1") (pintype "passive"))
      (node (ref "1N5400-8") (pin "1") (pintype "passive"))
      (node (ref "3.3K") (pin "2") (pinfunction "2_2") (pintype "passive"))
      (node (ref "47K") (pin "2") (pinfunction "2_2") (pintype "passive"))
      (node (ref "INPUT") (pin "P") (pinfunction "POS_P") (pintype "passive"))
    )
    (net (code "54") (name "Net-(LED-1-A)") (class "Default")
      (node (ref "47R-1") (pin "2") (pinfunction "2_2") (pintype "passive"))
      (node (ref "LED-1") (pin "1") (pinfunction "A_1") (pintype "passive"))
    )
    (net (code "55") (name "Net-(LED-1-K)") (class "Default")
      (node (ref "1N5400-2") (pin "2") (pintype "passive"))
      (node (ref "22K-1") (pin "2") (pinfunction "2_2") (pintype "passive"))
      (node (ref "2K-2") (pin "2") (pinfunction "2_2") (pintype "passive"))
      (node (ref "3.2K-2") (pin "1") (pinfunction "1_1") (pintype "passive"))
      (node (ref "BD438-2") (pin "E") (pinfunction "E_E") (pintype "passive"))
      (node (ref "LED-1") (pin "2") (pinfunction "K_2") (pintype "passive"))
      (node (ref "TL431-1") (pin "2") (pinfunction "ANODE_2") (pintype "passive"))
      (node (ref "cell-1") (pin "2") (pinfunction "2_2") (pintype "passive"))
    )
    (net (code "56") (name "Net-(LED-2-A)") (class "Default")
      (node (ref "47R-2") (pin "2") (pinfunction "2_2") (pintype "passive"))
      (node (ref "LED-2") (pin "1") (pinfunction "A_1") (pintype "passive"))
    )
    (net (code "57") (name "Net-(LED-2-K)") (class "Default")
      (node (ref "1N5400-5") (pin "2") (pintype "passive"))
      (node (ref "22K-2") (pin "2") (pinfunction "2_2") (pintype "passive"))
      (node (ref "2K-3") (pin "2") (pinfunction "2_2") (pintype "passive"))
      (node (ref "3.2K-3") (pin "1") (pinfunction "1_1") (pintype "passive"))
      (node (ref "BD438-3") (pin "E") (pinfunction "E_E") (pintype "passive"))
      (node (ref "LED-2") (pin "2") (pinfunction "K_2") (pintype "passive"))
      (node (ref "TL431-2") (pin "2") (pinfunction "ANODE_2") (pintype "passive"))
      (node (ref "cell-1") (pin "3") (pinfunction "3_3") (pintype "passive"))
    )
    (net (code "58") (name "Net-(LED-3-A)") (class "Default")
      (node (ref "47R-3") (pin "2") (pinfunction "2_2") (pintype "passive"))
      (node (ref "LED-3") (pin "1") (pinfunction "A_1") (pintype "passive"))
    )
    (net (code "59") (name "Net-(LED-3-K)") (class "Default")
      (node (ref "1N5400-7") (pin "2") (pintype "passive"))
      (node (ref "22K-3") (pin "2") (pinfunction "2_2") (pintype "passive"))
      (node (ref "LED-3") (pin "2") (pinfunction "K_2") (pintype "passive"))
      (node (ref "TIP122-1") (pin "2") (pinfunction "C_2") (pintype "passive"))
      (node (ref "TL431-3") (pin "2") (pinfunction "ANODE_2") (pintype "passive"))
      (node (ref "cell-1") (pin "4") (pinfunction "4_4") (pintype "passive"))
    )
    (net (code "60") (name "Net-(LED-4-A)") (class "Default")
      (node (ref "47R-4") (pin "2") (pinfunction "2_2") (pintype "passive"))
      (node (ref "LED-4") (pin "1") (pinfunction "A_1") (pintype "passive"))
    )
    (net (code "61") (name "Net-(LED-4-K)") (class "Default")
      (node (ref "1N5400-10") (pin "2") (pintype "passive"))
      (node (ref "22K-4") (pin "2") (pinfunction "2_2") (pintype "passive"))
      (node (ref "2K-5") (pin "2") (pinfunction "2_2") (pintype "passive"))
      (node (ref "3.2K-5") (pin "1") (pinfunction "1_1") (pintype "passive"))
      (node (ref "BD438-5") (pin "E") (pinfunction "E_E") (pintype "passive"))
      (node (ref "LED-4") (pin "2") (pinfunction "K_2") (pintype "passive"))
      (node (ref "TL431-4") (pin "2") (pinfunction "ANODE_2") (pintype "passive"))
      (node (ref "cell-2") (pin "2") (pinfunction "2_2") (pintype "passive"))
    )
    (net (code "62") (name "Net-(LED-5-A)") (class "Default")
      (node (ref "47R-5") (pin "2") (pinfunction "2_2") (pintype "passive"))
      (node (ref "LED-5") (pin "1") (pinfunction "A_1") (pintype "passive"))
    )
    (net (code "63") (name "Net-(LED-5-K)") (class "Default")
      (node (ref "1N5400-12") (pin "2") (pintype "passive"))
      (node (ref "22K-5") (pin "2") (pinfunction "2_2") (pintype "passive"))
      (node (ref "2K-6") (pin "2") (pinfunction "2_2") (pintype "passive"))
      (node (ref "3.2K-6") (pin "1") (pinfunction "1_1") (pintype "passive"))
      (node (ref "BD438-6") (pin "E") (pinfunction "E_E") (pintype "passive"))
      (node (ref "LED-5") (pin "2") (pinfunction "K_2") (pintype "passive"))
      (node (ref "TL431-5") (pin "2") (pinfunction "ANODE_2") (pintype "passive"))
      (node (ref "cell-2") (pin "3") (pinfunction "3_3") (pintype "passive"))
    )
    (net (code "64") (name "Net-(LED-6-A)") (class "Default")
      (node (ref "47R-6") (pin "2") (pinfunction "2_2") (pintype "passive"))
      (node (ref "LED-6") (pin "1") (pinfunction "A_1") (pintype "passive"))
    )
    (net (code "65") (name "Net-(LED-6-K)") (class "Default")
      (node (ref "1N5400-14") (pin "2") (pintype "passive"))
      (node (ref "22K-6") (pin "2") (pinfunction "2_2") (pintype "passive"))
      (node (ref "LED-6") (pin "2") (pinfunction "K_2") (pintype "passive"))
      (node (ref "TIP122-2") (pin "2") (pinfunction "C_2") (pintype "passive"))
      (node (ref "TL431-6") (pin "2") (pinfunction "ANODE_2") (pintype "passive"))
      (node (ref "cell-2") (pin "4") (pinfunction "4_4") (pintype "passive"))
    )
    (net (code "66") (name "Net-(LED-7-A)") (class "Default")
      (node (ref "47R-7") (pin "2") (pinfunction "2_2") (pintype "passive"))
      (node (ref "LED-7") (pin "1") (pinfunction "A_1") (pintype "passive"))
    )
    (net (code "67") (name "Net-(LED-7-K)") (class "Default")
      (node (ref "1N5400-17") (pin "2") (pintype "passive"))
      (node (ref "22K-7") (pin "2") (pinfunction "2_2") (pintype "passive"))
      (node (ref "2K-8") (pin "2") (pinfunction "2_2") (pintype "passive"))
      (node (ref "3.2K-8") (pin "1") (pinfunction "1_1") (pintype "passive"))
      (node (ref "BD438-8") (pin "E") (pinfunction "E_E") (pintype "passive"))
      (node (ref "LED-7") (pin "2") (pinfunction "K_2") (pintype "passive"))
      (node (ref "TL431-7") (pin "2") (pinfunction "ANODE_2") (pintype "passive"))
      (node (ref "cell-3") (pin "2") (pinfunction "2_2") (pintype "passive"))
    )
    (net (code "68") (name "Net-(LED-8-A)") (class "Default")
      (node (ref "47R-8") (pin "2") (pinfunction "2_2") (pintype "passive"))
      (node (ref "LED-8") (pin "1") (pinfunction "A_1") (pintype "passive"))
    )
    (net (code "69") (name "Net-(LED-8-K)") (class "Default")
      (node (ref "1N5400-19") (pin "2") (pintype "passive"))
      (node (ref "22K-8") (pin "2") (pinfunction "2_2") (pintype "passive"))
      (node (ref "2K-9") (pin "2") (pinfunction "2_2") (pintype "passive"))
      (node (ref "3.2K-9") (pin "1") (pinfunction "1_1") (pintype "passive"))
      (node (ref "BD438-9") (pin "E") (pinfunction "E_E") (pintype "passive"))
      (node (ref "LED-8") (pin "2") (pinfunction "K_2") (pintype "passive"))
      (node (ref "TL431-8") (pin "2") (pinfunction "ANODE_2") (pintype "passive"))
      (node (ref "cell-3") (pin "3") (pinfunction "3_3") (pintype "passive"))
    )
    (net (code "70") (name "Net-(LED-9-A)") (class "Default")
      (node (ref "47R-9") (pin "2") (pinfunction "2_2") (pintype "passive"))
      (node (ref "LED-9") (pin "1") (pinfunction "A_1") (pintype "passive"))
    )
    (net (code "71") (name "Net-(LED-9-K)") (class "Default")
      (node (ref "1N5400-21") (pin "2") (pintype "passive"))
      (node (ref "22K-9") (pin "2") (pinfunction "2_2") (pintype "passive"))
      (node (ref "LED-9") (pin "2") (pinfunction "K_2") (pintype "passive"))
      (node (ref "TIP122-3") (pin "2") (pinfunction "C_2") (pintype "passive"))
      (node (ref "TL431-9") (pin "2") (pinfunction "ANODE_2") (pintype "passive"))
      (node (ref "cell-3") (pin "4") (pinfunction "4_4") (pintype "passive"))
    )
    (net (code "72") (name "Net-(LED10-A)") (class "Default")
      (node (ref "3.3K") (pin "1") (pinfunction "1_1") (pintype "passive"))
      (node (ref "LED10") (pin "1") (pinfunction "A_1") (pintype "passive"))
    )
    (net (code "73") (name "Net-(TIP122-1-B)") (class "Default")
      (node (ref "2.2K-1") (pin "1") (pinfunction "1_1") (pintype "passive"))
      (node (ref "TIP122-1") (pin "1") (pinfunction "B_1") (pintype "passive"))
      (node (ref "TL431-10") (pin "1") (pinfunction "CATHODE_1") (pintype "passive"))
    )
    (net (code "74") (name "Net-(TIP122-1-E)") (class "Default")
      (node (ref "0.22R-1") (pin "2") (pinfunction "2_2") (pintype "passive"))
      (node (ref "TIP122-1") (pin "3") (pinfunction "E_3") (pintype "passive"))
    )
    (net (code "75") (name "Net-(TIP122-2-B)") (class "Default")
      (node (ref "2.2K-2") (pin "1") (pinfunction "1_1") (pintype "passive"))
      (node (ref "TIP122-2") (pin "1") (pinfunction "B_1") (pintype "passive"))
      (node (ref "TL431-11") (pin "1") (pinfunction "CATHODE_1") (pintype "passive"))
    )
    (net (code "76") (name "Net-(TIP122-2-E)") (class "Default")
      (node (ref "0.22R-2") (pin "2") (pinfunction "2_2") (pintype "passive"))
      (node (ref "TIP122-2") (pin "3") (pinfunction "E_3") (pintype "passive"))
    )
    (net (code "77") (name "Net-(TIP122-3-B)") (class "Default")
      (node (ref "2.2K-3") (pin "1") (pinfunction "1_1") (pintype "passive"))
      (node (ref "TIP122-3") (pin "1") (pinfunction "B_1") (pintype "passive"))
      (node (ref "TL431-12") (pin "1") (pinfunction "CATHODE_1") (pintype "passive"))
    )
    (net (code "78") (name "Net-(TIP122-3-E)") (class "Default")
      (node (ref "0.22R-3") (pin "2") (pinfunction "2_2") (pintype "passive"))
      (node (ref "TIP122-3") (pin "3") (pinfunction "E_3") (pintype "passive"))
    )
    (net (code "79") (name "Net-(TL431-1-CATHODE)") (class "Default")
      (node (ref "3.2K-1") (pin "2") (pinfunction "2_2") (pintype "passive"))
      (node (ref "BD438-1") (pin "B") (pinfunction "B_B") (pintype "passive"))
      (node (ref "TL431-1") (pin "1") (pinfunction "CATHODE_1") (pintype "passive"))
    )
    (net (code "80") (name "Net-(TL431-2-CATHODE)") (class "Default")
      (node (ref "3.2K-2") (pin "2") (pinfunction "2_2") (pintype "passive"))
      (node (ref "BD438-2") (pin "B") (pinfunction "B_B") (pintype "passive"))
      (node (ref "TL431-2") (pin "1") (pinfunction "CATHODE_1") (pintype "passive"))
    )
    (net (code "81") (name "Net-(TL431-3-CATHODE)") (class "Default")
      (node (ref "3.2K-3") (pin "2") (pinfunction "2_2") (pintype "passive"))
      (node (ref "BD438-3") (pin "B") (pinfunction "B_B") (pintype "passive"))
      (node (ref "TL431-3") (pin "1") (pinfunction "CATHODE_1") (pintype "passive"))
    )
    (net (code "82") (name "Net-(TL431-4-CATHODE)") (class "Default")
      (node (ref "3.2K-4") (pin "2") (pinfunction "2_2") (pintype "passive"))
      (node (ref "BD438-4") (pin "B") (pinfunction "B_B") (pintype "passive"))
      (node (ref "TL431-4") (pin "1") (pinfunction "CATHODE_1") (pintype "passive"))
    )
    (net (code "83") (name "Net-(TL431-5-CATHODE)") (class "Default")
      (node (ref "3.2K-5") (pin "2") (pinfunction "2_2") (pintype "passive"))
      (node (ref "BD438-5") (pin "B") (pinfunction "B_B") (pintype "passive"))
      (node (ref "TL431-5") (pin "1") (pinfunction "CATHODE_1") (pintype "passive"))
    )
    (net (code "84") (name "Net-(TL431-6-CATHODE)") (class "Default")
      (node (ref "3.2K-6") (pin "2") (pinfunction "2_2") (pintype "passive"))
      (node (ref "BD438-6") (pin "B") (pinfunction "B_B") (pintype "passive"))
      (node (ref "TL431-6") (pin "1") (pinfunction "CATHODE_1") (pintype "passive"))
    )
    (net (code "85") (name "Net-(TL431-7-CATHODE)") (class "Default")
      (node (ref "3.2K-7") (pin "2") (pinfunction "2_2") (pintype "passive"))
      (node (ref "BD438-7") (pin "B") (pinfunction "B_B") (pintype "passive"))
      (node (ref "TL431-7") (pin "1") (pinfunction "CATHODE_1") (pintype "passive"))
    )
    (net (code "86") (name "Net-(TL431-8-CATHODE)") (class "Default")
      (node (ref "3.2K-8") (pin "2") (pinfunction "2_2") (pintype "passive"))
      (node (ref "BD438-8") (pin "B") (pinfunction "B_B") (pintype "passive"))
      (node (ref "TL431-8") (pin "1") (pinfunction "CATHODE_1") (pintype "passive"))
    )
    (net (code "87") (name "Net-(TL431-9-CATHODE)") (class "Default")
      (node (ref "3.2K-9") (pin "2") (pinfunction "2_2") (pintype "passive"))
      (node (ref "BD438-9") (pin "B") (pinfunction "B_B") (pintype "passive"))
      (node (ref "TL431-9") (pin "1") (pinfunction "CATHODE_1") (pintype "passive"))
    )
  )
)
